# 7_can_rc_i2c_analog.net
KiCad netlist of a schematic drawn in Altium Designer
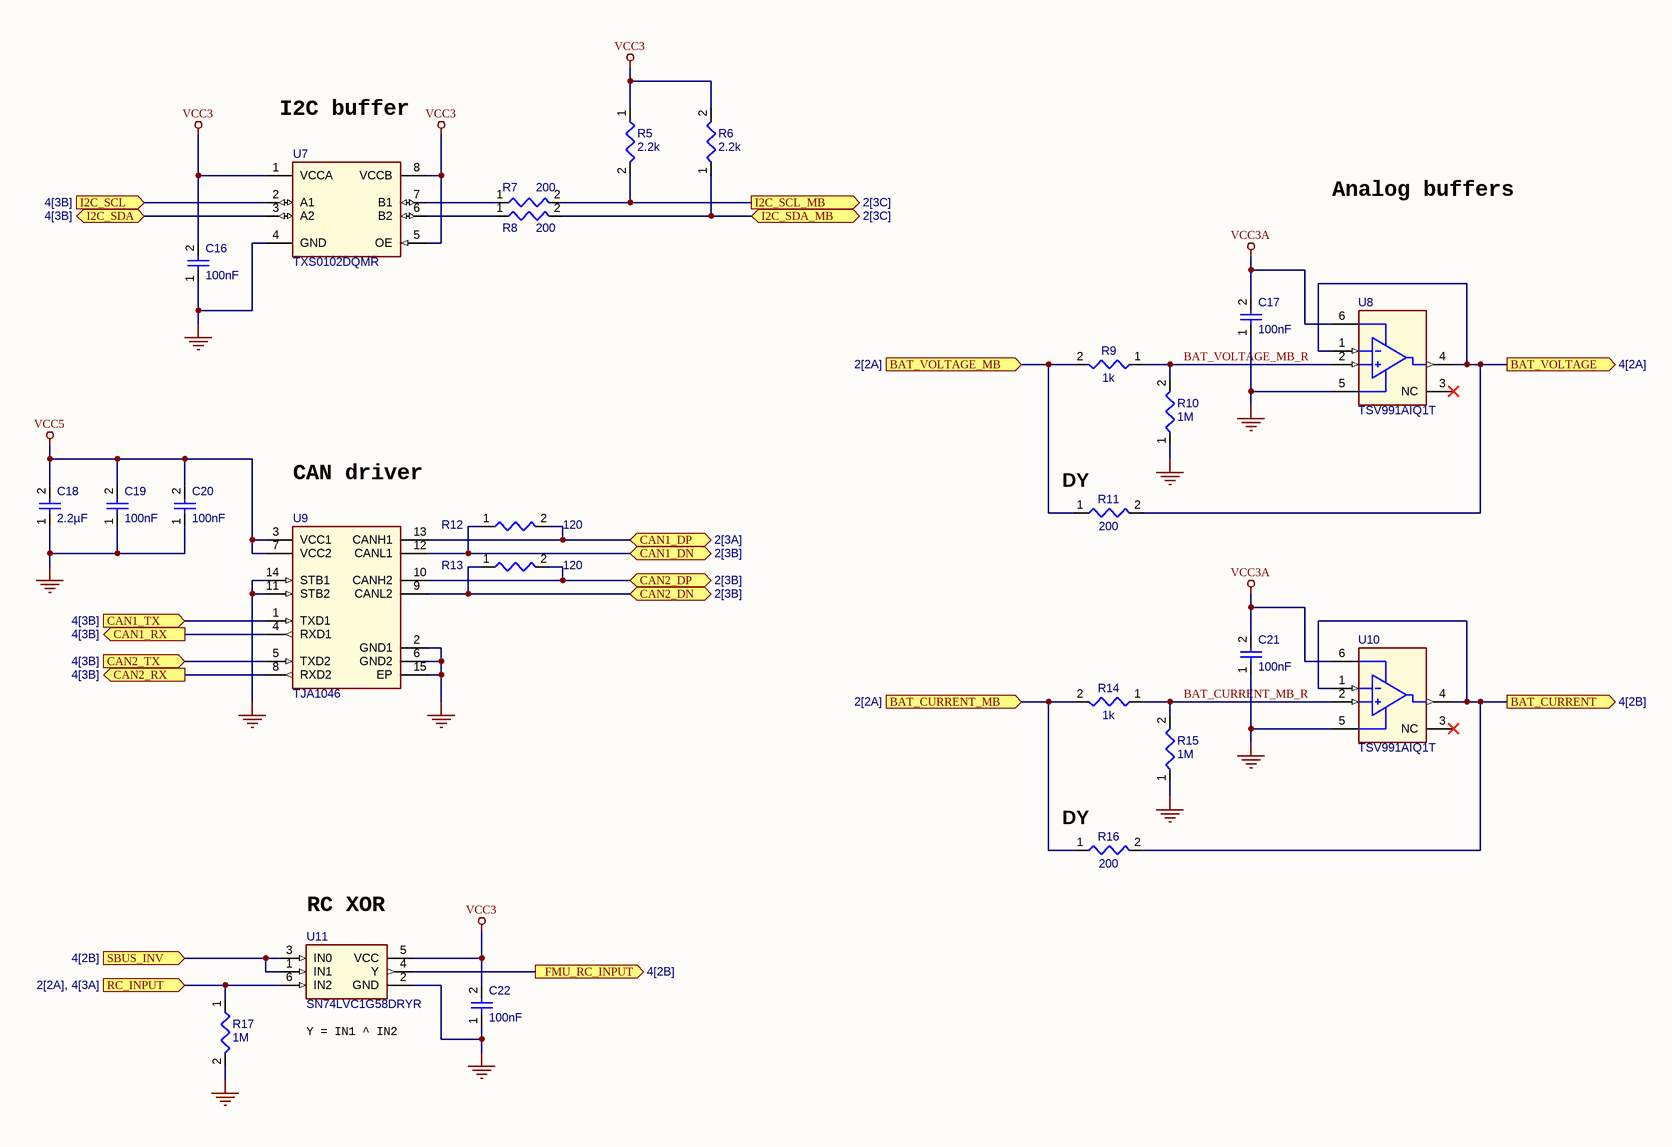
[diagram p0: 7_can_rc_i2c_analog.SchDoc]

(export (version "E")
  (design (tool "Eeschema 10.0.6"))
  (components
    (comp (ref "C16")
      (value "100nF")
      (footprint "CAPC0402(1005)60_L")
      (description "Chip Capacitor, 100nF +/-20%, 10V, 0402, Thickness 0.6 mm")
      (fields (field (name "TOLERANCE") "20%") (field (name "MANUFACTURER") "KEMET"))
      (libsource (lib "Kame_FMU") (part "Capacitor 100nF +/-20% 10V 0402"))
    )
    (comp (ref "C17")
      (value "100nF")
      (footprint "CAPC0402(1005)60_L")
      (description "Chip Capacitor, 100nF +/-20%, 10V, 0402, Thickness 0.6 mm")
      (fields (field (name "TOLERANCE") "20%") (field (name "MANUFACTURER") "KEMET"))
      (libsource (lib "Kame_FMU") (part "Capacitor 100nF +/-20% 10V 0402"))
    )
    (comp (ref "C18")
      (value "2.2µF")
      (footprint "CAPC0402(1005)60_L")
      (description "Chip Capacitor, 2,2µF +/-20%, 10V, 0402, Thickness 0.6 mm")
      (fields (field (name "TOLERANCE") "10%") (field (name "MANUFACTURER") "Murata"))
      (libsource (lib "Kame_FMU") (part "Capacitor 2,2µF +/-20% 10V 0402"))
    )
    (comp (ref "C19")
      (value "100nF")
      (footprint "CAPC0402(1005)60_L")
      (description "Chip Capacitor, 100nF +/-20%, 10V, 0402, Thickness 0.6 mm")
      (fields (field (name "TOLERANCE") "20%") (field (name "MANUFACTURER") "KEMET"))
      (libsource (lib "Kame_FMU") (part "Capacitor 100nF +/-20% 10V 0402"))
    )
    (comp (ref "C20")
      (value "100nF")
      (footprint "CAPC0402(1005)60_L")
      (description "Chip Capacitor, 100nF +/-20%, 10V, 0402, Thickness 0.6 mm")
      (fields (field (name "TOLERANCE") "20%") (field (name "MANUFACTURER") "KEMET"))
      (libsource (lib "Kame_FMU") (part "Capacitor 100nF +/-20% 10V 0402"))
    )
    (comp (ref "C21")
      (value "100nF")
      (footprint "CAPC0402(1005)60_L")
      (description "Chip Capacitor, 100nF +/-20%, 10V, 0402, Thickness 0.6 mm")
      (fields (field (name "TOLERANCE") "20%") (field (name "MANUFACTURER") "KEMET"))
      (libsource (lib "Kame_FMU") (part "Capacitor 100nF +/-20% 10V 0402"))
    )
    (comp (ref "C22")
      (value "100nF")
      (footprint "CAPC0402(1005)60_L")
      (description "Chip Capacitor, 100nF +/-20%, 10V, 0402, Thickness 0.6 mm")
      (fields (field (name "TOLERANCE") "20%") (field (name "MANUFACTURER") "KEMET"))
      (libsource (lib "Kame_FMU") (part "Capacitor 100nF +/-20% 10V 0402"))
    )
    (comp (ref "R5")
      (value "2.2k")
      (footprint "RESC0402(1005)_L")
      (description "Chip Resistor, 2,2 kOhms, +/-5 %, 63 mW, -55 to 155 degC, 0402")
      (fields (field (name "POWER") "63mW") (field (name "TOLERANCE") "5%"))
      (libsource (lib "Kame_FMU") (part "Resistor 2K2  +/-5 % 0402 63 mW"))
    )
    (comp (ref "R6")
      (value "2.2k")
      (footprint "RESC0402(1005)_L")
      (description "Chip Resistor, 2,2 kOhms, +/-5 %, 63 mW, -55 to 155 degC, 0402")
      (fields (field (name "POWER") "63mW") (field (name "TOLERANCE") "5%"))
      (libsource (lib "Kame_FMU") (part "Resistor 2K2  +/-5 % 0402 63 mW"))
    )
    (comp (ref "R7")
      (value "200")
      (footprint "RESC0402(1005)_L")
      (description "Chip Resistor, 200 Ohms, +/-5 %, 63 mW, -55 to 155 degC, 0402")
      (fields (field (name "POWER") "63mW") (field (name "TOLERANCE") "5%"))
      (libsource (lib "Kame_FMU") (part "Resistor 200R +/-5 % 0402 63 mW"))
    )
    (comp (ref "R8")
      (value "200")
      (footprint "RESC0402(1005)_L")
      (description "Chip Resistor, 200 Ohms, +/-5 %, 63 mW, -55 to 155 degC, 0402")
      (fields (field (name "POWER") "63mW") (field (name "TOLERANCE") "5%"))
      (libsource (lib "Kame_FMU") (part "Resistor 200R +/-5 % 0402 63 mW"))
    )
    (comp (ref "R9")
      (value "1k")
      (footprint "RESC0402(1005)_L")
      (description "Chip Resistor, 1 kOhms, +/-5 %, 63 mW, -55 to 155 degC, 0402")
      (fields (field (name "TOLERANCE") "5%") (field (name "POWER") "63mW"))
      (libsource (lib "Kame_FMU") (part "Resistor 1K +/-5 % 0402 63 mW"))
    )
    (comp (ref "R10")
      (value "1M")
      (footprint "RESC0402(1005)_L")
      (description "Chip Resistor, 1 MOhms, +/-5 %, 63 mW, -55 to 155 degC, 0402")
      (fields (field (name "TOLERANCE") "5%") (field (name "POWER") "63mW"))
      (libsource (lib "Kame_FMU") (part "Resistor 1M +/-5 % 0402 63 mW"))
    )
    (comp (ref "R11")
      (value "200")
      (footprint "RESC0402(1005)_L")
      (description "Chip Resistor, 200 Ohms, +/-5 %, 63 mW, -55 to 155 degC, 0402")
      (fields (field (name "POWER") "63mW") (field (name "TOLERANCE") "5%"))
      (libsource (lib "Kame_FMU") (part "Resistor 200R +/-5 % 0402 63 mW"))
    )
    (comp (ref "R12")
      (value "120")
      (footprint "RESC0603(1608)_L")
      (description "Chip Resistor, 120 Ohms, +/-5 %, 0.1 W, -55 to 155 degC, 0603")
      (fields (field (name "TOLERANCE") "5%") (field (name "POWER") "100mW"))
      (libsource (lib "Kame_FMU") (part "Resistor 120R +/-5 % 0603 0.1 W"))
    )
    (comp (ref "R13")
      (value "120")
      (footprint "RESC0603(1608)_L")
      (description "Chip Resistor, 120 Ohms, +/-5 %, 0.1 W, -55 to 155 degC, 0603")
      (fields (field (name "TOLERANCE") "5%") (field (name "POWER") "100mW"))
      (libsource (lib "Kame_FMU") (part "Resistor 120R +/-5 % 0603 0.1 W"))
    )
    (comp (ref "R14")
      (value "1k")
      (footprint "RESC0402(1005)_L")
      (description "Chip Resistor, 1 kOhms, +/-5 %, 63 mW, -55 to 155 degC, 0402")
      (fields (field (name "TOLERANCE") "5%") (field (name "POWER") "63mW"))
      (libsource (lib "Kame_FMU") (part "Resistor 1K +/-5 % 0402 63 mW"))
    )
    (comp (ref "R15")
      (value "1M")
      (footprint "RESC0402(1005)_L")
      (description "Chip Resistor, 1 MOhms, +/-5 %, 63 mW, -55 to 155 degC, 0402")
      (fields (field (name "TOLERANCE") "5%") (field (name "POWER") "63mW"))
      (libsource (lib "Kame_FMU") (part "Resistor 1M +/-5 % 0402 63 mW"))
    )
    (comp (ref "R16")
      (value "200")
      (footprint "RESC0402(1005)_L")
      (description "Chip Resistor, 200 Ohms, +/-5 %, 63 mW, -55 to 155 degC, 0402")
      (fields (field (name "POWER") "63mW") (field (name "TOLERANCE") "5%"))
      (libsource (lib "Kame_FMU") (part "Resistor 200R +/-5 % 0402 63 mW"))
    )
    (comp (ref "R17")
      (value "1M")
      (footprint "RESC0402(1005)_L")
      (description "Chip Resistor, 1 MOhms, +/-5 %, 63 mW, -55 to 155 degC, 0402")
      (fields (field (name "TOLERANCE") "5%") (field (name "POWER") "63mW"))
      (libsource (lib "Kame_FMU") (part "Resistor 1M +/-5 % 0402 63 mW"))
    )
    (comp (ref "U7")
      (value "TXS0102DQMR")
      (footprint "DQM")
      (description "IC TRANSLATOR VOLTAGE 8-X2SON")
      (fields (field (name "MANUFACTURER") "Texas Instruments"))
      (libsource (lib "Kame_FMU") (part "TXS0102DQMR"))
    )
    (comp (ref "U8")
      (value "TSV991AIQ1T")
      (footprint "STM-DFN-8_V")
      (fields (field (name "MANUFACTURER") "STMicroelectronics"))
      (libsource (lib "Kame_FMU") (part "TSV991AIQ1T"))
    )
    (comp (ref "U9")
      (value "TJA1046")
      (footprint "NXP-SOT1086-2_L")
      (fields
        (field (name "MANUFACTURER") "NXP Semiconductors")
        (field (name "MANUFACTURER PART NUMBER") "TJA1046TKZ")
      )
      (libsource (lib "Kame_FMU") (part "TJA1046"))
    )
    (comp (ref "U10")
      (value "TSV991AIQ1T")
      (footprint "STM-DFN-8_V")
      (fields (field (name "MANUFACTURER") "STMicroelectronics"))
      (libsource (lib "Kame_FMU") (part "TSV991AIQ1T"))
    )
    (comp (ref "U11")
      (value "SN74LVC1G58DRYR")
      (footprint "DRY0006A_V")
      (description "CONFIGURABLE MULTIPLE-FUNCTION GATE, DRY0006A, LARGE T&R")
      (fields (field (name "MANUFACTURER") "Texas Instruments"))
      (libsource (lib "Kame_FMU") (part "SN74LVC1G58DRYR"))
    )
  )
  (nets
    (net (code "1") (name "/BAT_CURRENT") (class "Default")
      (node (ref "R16") (pin "2") (pinfunction "2_2") (pintype "passive"))
      (node (ref "U10") (pin "1") (pinfunction "IN-_1") (pintype "input"))
      (node (ref "U10") (pin "4") (pinfunction "OUT_4") (pintype "output"))
    )
    (net (code "2") (name "/BAT_CURRENT_MB") (class "Default")
      (node (ref "R14") (pin "2") (pinfunction "2_2") (pintype "passive"))
      (node (ref "R16") (pin "1") (pinfunction "1_1") (pintype "passive"))
    )
    (net (code "3") (name "/BAT_CURRENT_MB_R") (class "Default")
      (node (ref "R14") (pin "1") (pinfunction "1_1") (pintype "passive"))
      (node (ref "R15") (pin "2") (pinfunction "2_2") (pintype "passive"))
      (node (ref "U10") (pin "2") (pinfunction "IN+_2") (pintype "input"))
    )
    (net (code "4") (name "/BAT_VOLTAGE") (class "Default")
      (node (ref "R11") (pin "2") (pinfunction "2_2") (pintype "passive"))
      (node (ref "U8") (pin "1") (pinfunction "IN-_1") (pintype "input"))
      (node (ref "U8") (pin "4") (pinfunction "OUT_4") (pintype "output"))
    )
    (net (code "5") (name "/BAT_VOLTAGE_MB") (class "Default")
      (node (ref "R11") (pin "1") (pinfunction "1_1") (pintype "passive"))
      (node (ref "R9") (pin "2") (pinfunction "2_2") (pintype "passive"))
    )
    (net (code "6") (name "/BAT_VOLTAGE_MB_R") (class "Default")
      (node (ref "R10") (pin "2") (pinfunction "2_2") (pintype "passive"))
      (node (ref "R9") (pin "1") (pinfunction "1_1") (pintype "passive"))
      (node (ref "U8") (pin "2") (pinfunction "IN+_2") (pintype "input"))
    )
    (net (code "7") (name "/CAN1_DN") (class "Default")
      (node (ref "R12") (pin "1") (pinfunction "1_1") (pintype "passive"))
      (node (ref "U9") (pin "12") (pinfunction "CANL1_12") (pintype "passive"))
    )
    (net (code "8") (name "/CAN1_DP") (class "Default")
      (node (ref "R12") (pin "2") (pinfunction "2_2") (pintype "passive"))
      (node (ref "U9") (pin "13") (pinfunction "CANH1_13") (pintype "passive"))
    )
    (net (code "9") (name "/CAN1_RX") (class "Default")
      (node (ref "U9") (pin "4") (pinfunction "RXD1_4") (pintype "output"))
    )
    (net (code "10") (name "/CAN1_TX") (class "Default")
      (node (ref "U9") (pin "1") (pinfunction "TXD1_1") (pintype "input"))
    )
    (net (code "11") (name "/CAN2_DN") (class "Default")
      (node (ref "R13") (pin "1") (pinfunction "1_1") (pintype "passive"))
      (node (ref "U9") (pin "9") (pinfunction "CANL2_9") (pintype "passive"))
    )
    (net (code "12") (name "/CAN2_DP") (class "Default")
      (node (ref "R13") (pin "2") (pinfunction "2_2") (pintype "passive"))
      (node (ref "U9") (pin "10") (pinfunction "CANH2_10") (pintype "passive"))
    )
    (net (code "13") (name "/CAN2_RX") (class "Default")
      (node (ref "U9") (pin "8") (pinfunction "RXD2_8") (pintype "output"))
    )
    (net (code "14") (name "/CAN2_TX") (class "Default")
      (node (ref "U9") (pin "5") (pinfunction "TXD2_5") (pintype "input"))
    )
    (net (code "15") (name "/FMU_RC_INPUT") (class "Default")
      (node (ref "U11") (pin "4") (pinfunction "Y_4") (pintype "output"))
    )
    (net (code "16") (name "/I2C_SCL") (class "Default")
      (node (ref "U7") (pin "2") (pinfunction "A1_2") (pintype "bidirectional"))
    )
    (net (code "17") (name "/I2C_SCL_MB") (class "Default")
      (node (ref "R5") (pin "2") (pinfunction "2_2") (pintype "passive"))
      (node (ref "R7") (pin "2") (pinfunction "2_2") (pintype "passive"))
    )
    (net (code "18") (name "/I2C_SDA") (class "Default")
      (node (ref "U7") (pin "3") (pinfunction "A2_3") (pintype "bidirectional"))
    )
    (net (code "19") (name "/I2C_SDA_MB") (class "Default")
      (node (ref "R6") (pin "1") (pinfunction "1_1") (pintype "passive"))
      (node (ref "R8") (pin "2") (pinfunction "2_2") (pintype "passive"))
    )
    (net (code "20") (name "/RC_INPUT") (class "Default")
      (node (ref "R17") (pin "1") (pinfunction "1_1") (pintype "passive"))
      (node (ref "U11") (pin "6") (pinfunction "IN2_6") (pintype "input"))
    )
    (net (code "21") (name "/SBUS_INV") (class "Default")
      (node (ref "U11") (pin "1") (pinfunction "IN1_1") (pintype "input"))
      (node (ref "U11") (pin "3") (pinfunction "IN0_3") (pintype "input"))
    )
    (net (code "22") (name "GND") (class "Default")
      (node (ref "C16") (pin "1") (pinfunction "1_1") (pintype "passive"))
      (node (ref "C17") (pin "1") (pinfunction "1_1") (pintype "passive"))
      (node (ref "C18") (pin "1") (pinfunction "1_1") (pintype "passive"))
      (node (ref "C19") (pin "1") (pinfunction "1_1") (pintype "passive"))
      (node (ref "C20") (pin "1") (pinfunction "1_1") (pintype "passive"))
      (node (ref "C21") (pin "1") (pinfunction "1_1") (pintype "passive"))
      (node (ref "C22") (pin "1") (pinfunction "1_1") (pintype "passive"))
      (node (ref "R10") (pin "1") (pinfunction "1_1") (pintype "passive"))
      (node (ref "R15") (pin "1") (pinfunction "1_1") (pintype "passive"))
      (node (ref "R17") (pin "2") (pinfunction "2_2") (pintype "passive"))
      (node (ref "U10") (pin "5") (pinfunction "VCC-_5") (pintype "power_in"))
      (node (ref "U11") (pin "2") (pinfunction "GND_2") (pintype "power_in"))
      (node (ref "U7") (pin "4") (pinfunction "GND_4") (pintype "power_in"))
      (node (ref "U8") (pin "5") (pinfunction "VCC-_5") (pintype "power_in"))
      (node (ref "U9") (pin "11") (pinfunction "STB2_11") (pintype "input"))
      (node (ref "U9") (pin "14") (pinfunction "STB1_14") (pintype "input"))
      (node (ref "U9") (pin "15") (pinfunction "EP_15") (pintype "power_in"))
      (node (ref "U9") (pin "2") (pinfunction "GND1_2") (pintype "power_in"))
      (node (ref "U9") (pin "6") (pinfunction "GND2_6") (pintype "power_in"))
    )
    (net (code "23") (name "Net-(U7-B1)") (class "Default")
      (node (ref "R7") (pin "1") (pinfunction "1_1") (pintype "passive"))
      (node (ref "U7") (pin "7") (pinfunction "B1_7") (pintype "bidirectional"))
    )
    (net (code "24") (name "Net-(U7-B2)") (class "Default")
      (node (ref "R8") (pin "1") (pinfunction "1_1") (pintype "passive"))
      (node (ref "U7") (pin "6") (pinfunction "B2_6") (pintype "bidirectional"))
    )
    (net (code "25") (name "VCC3") (class "Default")
      (node (ref "C16") (pin "2") (pinfunction "2_2") (pintype "passive"))
      (node (ref "C22") (pin "2") (pinfunction "2_2") (pintype "passive"))
      (node (ref "R5") (pin "1") (pinfunction "1_1") (pintype "passive"))
      (node (ref "R6") (pin "2") (pinfunction "2_2") (pintype "passive"))
      (node (ref "U11") (pin "5") (pinfunction "VCC_5") (pintype "power_in"))
      (node (ref "U7") (pin "1") (pinfunction "VCCA_1") (pintype "power_in"))
      (node (ref "U7") (pin "5") (pinfunction "OE_5") (pintype "input"))
      (node (ref "U7") (pin "8") (pinfunction "VCCB_8") (pintype "power_in"))
    )
    (net (code "26") (name "VCC3A") (class "Default")
      (node (ref "C17") (pin "2") (pinfunction "2_2") (pintype "passive"))
      (node (ref "C21") (pin "2") (pinfunction "2_2") (pintype "passive"))
      (node (ref "U10") (pin "6") (pinfunction "VCC+_6") (pintype "power_in"))
      (node (ref "U8") (pin "6") (pinfunction "VCC+_6") (pintype "power_in"))
    )
    (net (code "27") (name "VCC5") (class "Default")
      (node (ref "C18") (pin "2") (pinfunction "2_2") (pintype "passive"))
      (node (ref "C19") (pin "2") (pinfunction "2_2") (pintype "passive"))
      (node (ref "C20") (pin "2") (pinfunction "2_2") (pintype "passive"))
      (node (ref "U9") (pin "3") (pinfunction "VCC1_3") (pintype "power_in"))
      (node (ref "U9") (pin "7") (pinfunction "VCC2_7") (pintype "power_in"))
    )
    (net (code "28") (name "unconnected-(U8-NC-Pad3)") (class "Default")
      (node (ref "U8") (pin "3") (pinfunction "NC_3") (pintype "passive+no_connect"))
    )
    (net (code "29") (name "unconnected-(U10-NC-Pad3)") (class "Default")
      (node (ref "U10") (pin "3") (pinfunction "NC_3") (pintype "passive+no_connect"))
    )
  )
)
